# HB-UNI-SenAct-4-4-RC_V2_1.net
KiCad netlist of a schematic drawn in EAGLE
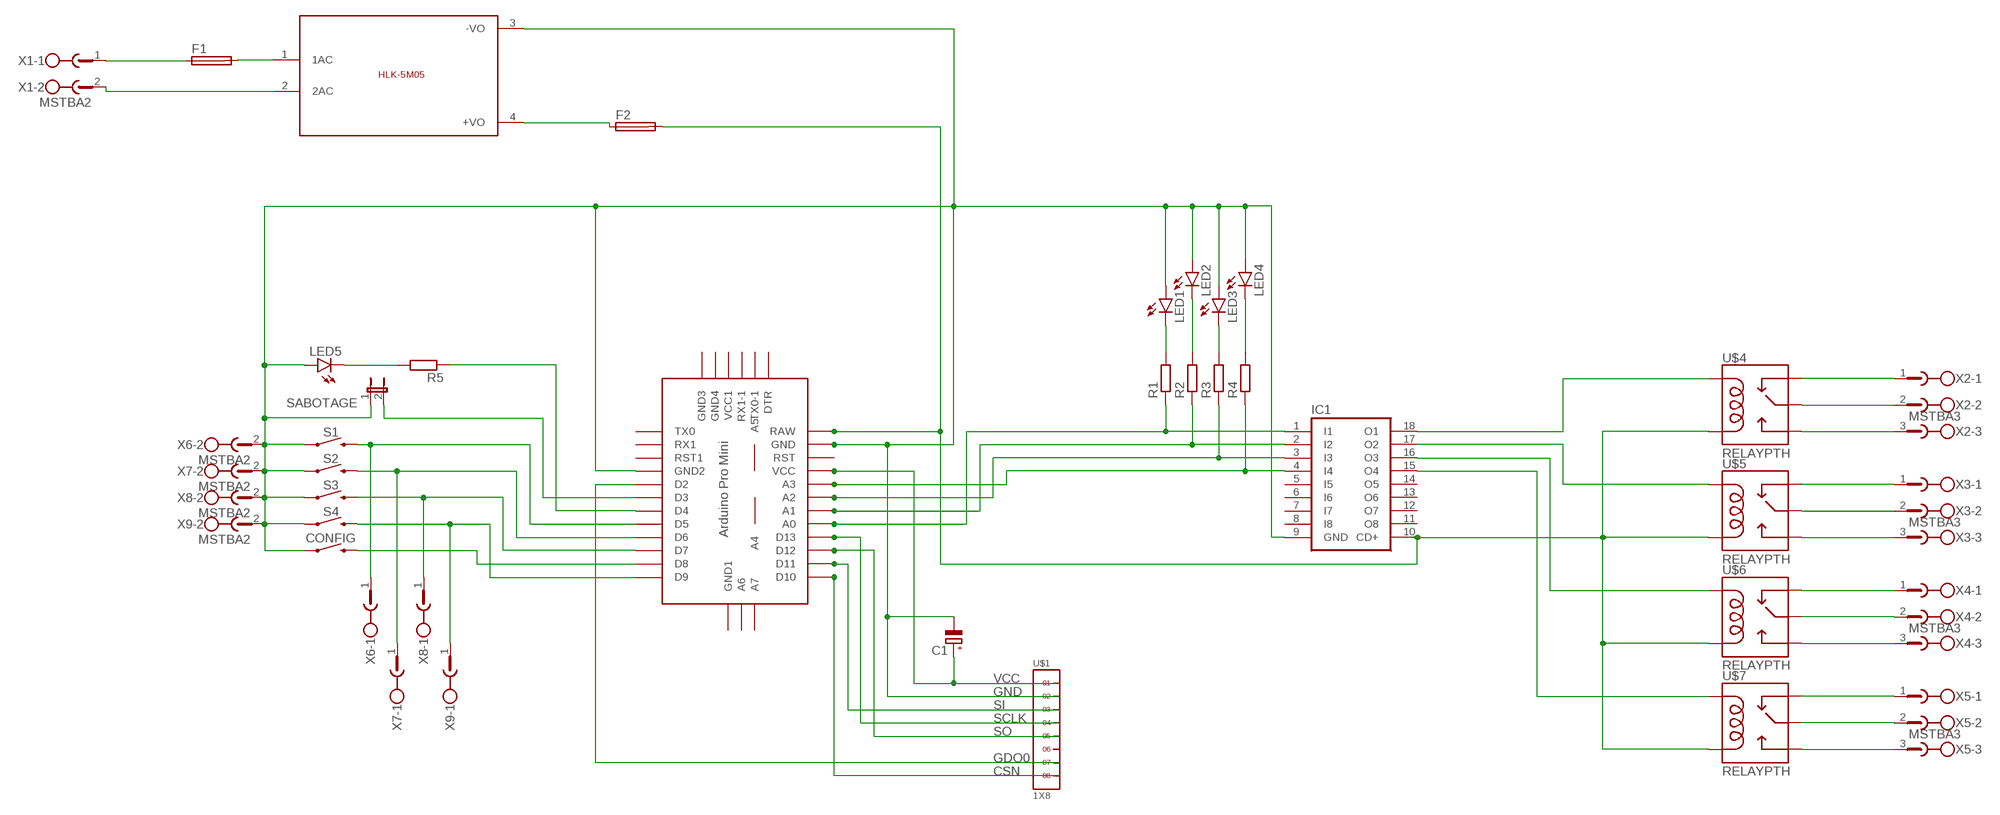
[diagram p0: schematic, sheet 1]

(export (version "E")
  (design (tool "Eeschema 10.0.6"))
  (components
    (comp (ref "C1")
      (value "CPOL-EUE2.5-5")
      (footprint "eagle-import:E2,5-5")
      (libsource (lib "eagle-import") (part "CPOL-EUE2.5-5"))
    )
    (comp (ref "CONFIG")
      (value "MOMENTARY-SWITCH-SPST-PTH-6.0MM-KIT")
      (footprint "eagle-import:TACTILE_SWITCH_PTH_6.0MM_KIT")
      (libsource (lib "eagle-import") (part "MOMENTARY-SWITCH-SPST-PTH-6.0MM-KIT"))
    )
    (comp (ref "F1")
      (value "SH22,5A")
      (footprint "eagle-import:SH22,5A")
      (fields (field (name "MPN") "0031.7701.11"))
      (libsource (lib "eagle-import") (part "SH22,5A"))
    )
    (comp (ref "F2")
      (value "SH22,5A")
      (footprint "eagle-import:SH22,5A")
      (fields (field (name "MPN") "0031.7701.11"))
      (libsource (lib "eagle-import") (part "SH22,5A"))
    )
    (comp (ref "IC1")
      (value "ULN2803A")
      (footprint "eagle-import:DIL18")
      (libsource (lib "eagle-import") (part "ULN2803A"))
    )
    (comp (ref "LED1")
      (value "LED3MM")
      (footprint "eagle-import:LED3MM")
      (libsource (lib "eagle-import") (part "LED3MM"))
    )
    (comp (ref "LED2")
      (value "LED3MM")
      (footprint "eagle-import:LED3MM")
      (libsource (lib "eagle-import") (part "LED3MM"))
    )
    (comp (ref "LED3")
      (value "LED3MM")
      (footprint "eagle-import:LED3MM")
      (libsource (lib "eagle-import") (part "LED3MM"))
    )
    (comp (ref "LED4")
      (value "LED3MM")
      (footprint "eagle-import:LED3MM")
      (libsource (lib "eagle-import") (part "LED3MM"))
    )
    (comp (ref "LED5")
      (value "LED3MM")
      (footprint "eagle-import:LED3MM")
      (libsource (lib "eagle-import") (part "LED3MM"))
    )
    (comp (ref "R1")
      (value "R-EU_0309/10")
      (footprint "eagle-import:0309_10")
      (libsource (lib "eagle-import") (part "R-EU_0309/10"))
    )
    (comp (ref "R2")
      (value "R-EU_0309/10")
      (footprint "eagle-import:0309_10")
      (libsource (lib "eagle-import") (part "R-EU_0309/10"))
    )
    (comp (ref "R3")
      (value "R-EU_0309/10")
      (footprint "eagle-import:0309_10")
      (libsource (lib "eagle-import") (part "R-EU_0309/10"))
    )
    (comp (ref "R4")
      (value "R-EU_0309/10")
      (footprint "eagle-import:0309_10")
      (libsource (lib "eagle-import") (part "R-EU_0309/10"))
    )
    (comp (ref "R5")
      (value "R-EU_0309/10")
      (footprint "eagle-import:0309_10")
      (libsource (lib "eagle-import") (part "R-EU_0309/10"))
    )
    (comp (ref "S1")
      (value "MOMENTARY-SWITCH-SPST-PTH-6.0MM")
      (footprint "eagle-import:TACTILE_SWITCH_PTH_6.0MM")
      (libsource (lib "eagle-import") (part "MOMENTARY-SWITCH-SPST-PTH-6.0MM"))
    )
    (comp (ref "S2")
      (value "MOMENTARY-SWITCH-SPST-PTH-6.0MM-KIT")
      (footprint "eagle-import:TACTILE_SWITCH_PTH_6.0MM_KIT")
      (libsource (lib "eagle-import") (part "MOMENTARY-SWITCH-SPST-PTH-6.0MM-KIT"))
    )
    (comp (ref "S3")
      (value "MOMENTARY-SWITCH-SPST-PTH-6.0MM-KIT")
      (footprint "eagle-import:TACTILE_SWITCH_PTH_6.0MM_KIT")
      (libsource (lib "eagle-import") (part "MOMENTARY-SWITCH-SPST-PTH-6.0MM-KIT"))
    )
    (comp (ref "S4")
      (value "MOMENTARY-SWITCH-SPST-PTH-6.0MM-KIT")
      (footprint "eagle-import:TACTILE_SWITCH_PTH_6.0MM_KIT")
      (libsource (lib "eagle-import") (part "MOMENTARY-SWITCH-SPST-PTH-6.0MM-KIT"))
    )
    (comp (ref "SABOTAGE")
      (value "JP1E")
      (footprint "eagle-import:JP1")
      (libsource (lib "eagle-import") (part "JP1E"))
    )
    (comp (ref "U$1")
      (value "1X8")
      (footprint "eagle-import:1X8")
      (libsource (lib "eagle-import") (part "1X8"))
    )
    (comp (ref "U$2")
      (value "ABK-PRO-MINI")
      (footprint "eagle-import:ABK-PRO-MINI")
      (libsource (lib "eagle-import") (part "ABK-PRO-MINI"))
    )
    (comp (ref "U$3")
      (value "5VDC/5W")
      (footprint "eagle-import:HLK-5M05")
      (libsource (lib "eagle-import") (part "HLK-5M05"))
    )
    (comp (ref "U$4")
      (value "RELAYPTH")
      (footprint "eagle-import:SRD-05VDC-SL-C")
      (libsource (lib "eagle-import") (part "RELAYPTH"))
    )
    (comp (ref "U$5")
      (value "RELAYPTH")
      (footprint "eagle-import:SRD-05VDC-SL-C")
      (libsource (lib "eagle-import") (part "RELAYPTH"))
    )
    (comp (ref "U$6")
      (value "RELAYPTH")
      (footprint "eagle-import:SRD-05VDC-SL-C")
      (libsource (lib "eagle-import") (part "RELAYPTH"))
    )
    (comp (ref "U$7")
      (value "RELAYPTH")
      (footprint "eagle-import:SRD-05VDC-SL-C")
      (libsource (lib "eagle-import") (part "RELAYPTH"))
    )
    (comp (ref "X1")
      (value "MSTBA2")
      (footprint "eagle-import:MSTBA2")
      (fields (field (name "MF") "FARNELL") (field (name "MPN") "1757242"))
      (libsource (lib "eagle-import") (part "MSTBA2"))
    )
    (comp (ref "X2")
      (value "MSTBA3")
      (footprint "eagle-import:MSTBA3")
      (fields (field (name "MF") "FARNELL") (field (name "MPN") "1757255"))
      (libsource (lib "eagle-import") (part "MSTBA3"))
    )
    (comp (ref "X3")
      (value "MSTBA3")
      (footprint "eagle-import:MSTBA3")
      (fields (field (name "MF") "FARNELL") (field (name "MPN") "1757255"))
      (libsource (lib "eagle-import") (part "MSTBA3"))
    )
    (comp (ref "X4")
      (value "MSTBA3")
      (footprint "eagle-import:MSTBA3")
      (fields (field (name "MF") "FARNELL") (field (name "MPN") "1757255"))
      (libsource (lib "eagle-import") (part "MSTBA3"))
    )
    (comp (ref "X5")
      (value "MSTBA3")
      (footprint "eagle-import:MSTBA3")
      (fields (field (name "MF") "FARNELL") (field (name "MPN") "1757255"))
      (libsource (lib "eagle-import") (part "MSTBA3"))
    )
    (comp (ref "X6")
      (value "MSTBA2")
      (footprint "eagle-import:MSTBA2")
      (fields (field (name "MF") "FARNELL") (field (name "MPN") "1757242"))
      (libsource (lib "eagle-import") (part "MSTBA2"))
    )
    (comp (ref "X7")
      (value "MSTBA2")
      (footprint "eagle-import:MSTBA2")
      (fields (field (name "MF") "FARNELL") (field (name "MPN") "1757242"))
      (libsource (lib "eagle-import") (part "MSTBA2"))
    )
    (comp (ref "X8")
      (value "MSTBA2")
      (footprint "eagle-import:MSTBA2")
      (fields (field (name "MF") "FARNELL") (field (name "MPN") "1757242"))
      (libsource (lib "eagle-import") (part "MSTBA2"))
    )
    (comp (ref "X9")
      (value "MSTBA2")
      (footprint "eagle-import:MSTBA2")
      (fields (field (name "MF") "FARNELL") (field (name "MPN") "1757242"))
      (libsource (lib "eagle-import") (part "MSTBA2"))
    )
  )
  (nets
    (net (code "1") (name "/CSN") (class "Default")
      (node (ref "U$1") (pin "8") (pinfunction "8_8") (pintype "bidirectional"))
      (node (ref "U$2") (pin "D10") (pinfunction "D10_D10") (pintype "bidirectional"))
    )
    (net (code "2") (name "/GDO0") (class "Default")
      (node (ref "U$1") (pin "7") (pinfunction "7_7") (pintype "bidirectional"))
      (node (ref "U$2") (pin "D2") (pinfunction "D2_D2") (pintype "bidirectional"))
    )
    (net (code "3") (name "/GND") (class "Default")
      (node (ref "C1") (pin "-") (pinfunction "-_-") (pintype "passive"))
      (node (ref "CONFIG") (pin "1") (pinfunction "1_1") (pintype "passive"))
      (node (ref "IC1") (pin "9") (pinfunction "GND_9") (pintype "power_in"))
      (node (ref "LED1") (pin "A") (pinfunction "A_A") (pintype "passive"))
      (node (ref "LED2") (pin "A") (pinfunction "A_A") (pintype "passive"))
      (node (ref "LED3") (pin "A") (pinfunction "A_A") (pintype "passive"))
      (node (ref "LED4") (pin "A") (pinfunction "A_A") (pintype "passive"))
      (node (ref "LED5") (pin "A") (pinfunction "A_A") (pintype "passive"))
      (node (ref "S1") (pin "1") (pinfunction "1_1") (pintype "passive"))
      (node (ref "S2") (pin "1") (pinfunction "1_1") (pintype "passive"))
      (node (ref "S3") (pin "1") (pinfunction "1_1") (pintype "passive"))
      (node (ref "S4") (pin "1") (pinfunction "1_1") (pintype "passive"))
      (node (ref "SABOTAGE") (pin "1") (pinfunction "1_1") (pintype "passive"))
      (node (ref "U$1") (pin "2") (pinfunction "2_2") (pintype "bidirectional"))
      (node (ref "U$2") (pin "GND") (pinfunction "GND_GND") (pintype "bidirectional"))
      (node (ref "U$2") (pin "GND1") (pinfunction "GND2_GND1") (pintype "bidirectional"))
      (node (ref "U$3") (pin "3") (pinfunction "-VO_3") (pintype "bidirectional"))
      (node (ref "X6") (pin "2") (pinfunction "1_2") (pintype "passive"))
      (node (ref "X7") (pin "2") (pinfunction "1_2") (pintype "passive"))
      (node (ref "X8") (pin "2") (pinfunction "1_2") (pintype "passive"))
      (node (ref "X9") (pin "2") (pinfunction "1_2") (pintype "passive"))
    )
    (net (code "4") (name "/SCLK") (class "Default")
      (node (ref "U$1") (pin "4") (pinfunction "4_4") (pintype "bidirectional"))
      (node (ref "U$2") (pin "D13") (pinfunction "D13_D13") (pintype "bidirectional"))
    )
    (net (code "5") (name "/SI") (class "Default")
      (node (ref "U$1") (pin "3") (pinfunction "3_3") (pintype "bidirectional"))
      (node (ref "U$2") (pin "D11") (pinfunction "D11_D11") (pintype "bidirectional"))
    )
    (net (code "6") (name "/SO") (class "Default")
      (node (ref "U$1") (pin "5") (pinfunction "5_5") (pintype "bidirectional"))
      (node (ref "U$2") (pin "D12") (pinfunction "D12_D12") (pintype "bidirectional"))
    )
    (net (code "7") (name "/VCC") (class "Default")
      (node (ref "C1") (pin "+") (pinfunction "+_+") (pintype "passive"))
      (node (ref "U$1") (pin "1") (pinfunction "1_1") (pintype "bidirectional"))
      (node (ref "U$2") (pin "VCC") (pinfunction "VCC_VCC") (pintype "bidirectional"))
    )
    (net (code "8") (name "Net-(CONFIG-2)") (class "Default")
      (node (ref "CONFIG") (pin "3") (pinfunction "2_3") (pintype "passive"))
      (node (ref "U$2") (pin "D8") (pinfunction "D8_D8") (pintype "bidirectional"))
    )
    (net (code "9") (name "Net-(F1-Pad1)") (class "Default")
      (node (ref "F1") (pin "1") (pinfunction "1_1") (pintype "passive"))
      (node (ref "X1") (pin "1") (pinfunction "1_1") (pintype "passive"))
    )
    (net (code "10") (name "Net-(IC1-CD+)") (class "Default")
      (node (ref "F2") (pin "2") (pinfunction "2_2") (pintype "passive"))
      (node (ref "IC1") (pin "10") (pinfunction "CD+_10") (pintype "passive"))
      (node (ref "U$2") (pin "RAW") (pinfunction "RAW_RAW") (pintype "bidirectional"))
      (node (ref "U$4") (pin "COIL0") (pinfunction "COIL0_COIL0") (pintype "bidirectional"))
      (node (ref "U$5") (pin "COIL0") (pinfunction "COIL0_COIL0") (pintype "bidirectional"))
      (node (ref "U$6") (pin "COIL0") (pinfunction "COIL0_COIL0") (pintype "bidirectional"))
      (node (ref "U$7") (pin "COIL0") (pinfunction "COIL0_COIL0") (pintype "bidirectional"))
    )
    (net (code "11") (name "Net-(IC1-I1)") (class "Default")
      (node (ref "IC1") (pin "1") (pinfunction "I1_1") (pintype "input"))
      (node (ref "R1") (pin "1") (pinfunction "1_1") (pintype "passive"))
      (node (ref "U$2") (pin "A0") (pinfunction "A0_A0") (pintype "bidirectional"))
    )
    (net (code "12") (name "Net-(IC1-I2)") (class "Default")
      (node (ref "IC1") (pin "2") (pinfunction "I2_2") (pintype "input"))
      (node (ref "R2") (pin "1") (pinfunction "1_1") (pintype "passive"))
      (node (ref "U$2") (pin "A1") (pinfunction "A1_A1") (pintype "bidirectional"))
    )
    (net (code "13") (name "Net-(IC1-I3)") (class "Default")
      (node (ref "IC1") (pin "3") (pinfunction "I3_3") (pintype "input"))
      (node (ref "R3") (pin "1") (pinfunction "1_1") (pintype "passive"))
      (node (ref "U$2") (pin "A2") (pinfunction "A2_A2") (pintype "bidirectional"))
    )
    (net (code "14") (name "Net-(IC1-I4)") (class "Default")
      (node (ref "IC1") (pin "4") (pinfunction "I4_4") (pintype "input"))
      (node (ref "R4") (pin "1") (pinfunction "1_1") (pintype "passive"))
      (node (ref "U$2") (pin "A3") (pinfunction "A3_A3") (pintype "bidirectional"))
    )
    (net (code "15") (name "Net-(IC1-O1)") (class "Default")
      (node (ref "IC1") (pin "18") (pinfunction "O1_18") (pintype "open_collector"))
      (node (ref "U$4") (pin "COIL1") (pinfunction "COIL1_COIL1") (pintype "bidirectional"))
    )
    (net (code "16") (name "Net-(IC1-O2)") (class "Default")
      (node (ref "IC1") (pin "17") (pinfunction "O2_17") (pintype "open_collector"))
      (node (ref "U$5") (pin "COIL1") (pinfunction "COIL1_COIL1") (pintype "bidirectional"))
    )
    (net (code "17") (name "Net-(IC1-O3)") (class "Default")
      (node (ref "IC1") (pin "16") (pinfunction "O3_16") (pintype "open_collector"))
      (node (ref "U$6") (pin "COIL1") (pinfunction "COIL1_COIL1") (pintype "bidirectional"))
    )
    (net (code "18") (name "Net-(IC1-O4)") (class "Default")
      (node (ref "IC1") (pin "15") (pinfunction "O4_15") (pintype "open_collector"))
      (node (ref "U$7") (pin "COIL1") (pinfunction "COIL1_COIL1") (pintype "bidirectional"))
    )
    (net (code "19") (name "Net-(LED1-C)") (class "Default")
      (node (ref "LED1") (pin "K") (pinfunction "C_K") (pintype "passive"))
      (node (ref "R1") (pin "2") (pinfunction "2_2") (pintype "passive"))
    )
    (net (code "20") (name "Net-(LED2-C)") (class "Default")
      (node (ref "LED2") (pin "K") (pinfunction "C_K") (pintype "passive"))
      (node (ref "R2") (pin "2") (pinfunction "2_2") (pintype "passive"))
    )
    (net (code "21") (name "Net-(LED3-C)") (class "Default")
      (node (ref "LED3") (pin "K") (pinfunction "C_K") (pintype "passive"))
      (node (ref "R3") (pin "2") (pinfunction "2_2") (pintype "passive"))
    )
    (net (code "22") (name "Net-(LED4-C)") (class "Default")
      (node (ref "LED4") (pin "K") (pinfunction "C_K") (pintype "passive"))
      (node (ref "R4") (pin "2") (pinfunction "2_2") (pintype "passive"))
    )
    (net (code "23") (name "Net-(LED5-C)") (class "Default")
      (node (ref "LED5") (pin "K") (pinfunction "C_K") (pintype "passive"))
      (node (ref "R5") (pin "2") (pinfunction "2_2") (pintype "passive"))
    )
    (net (code "24") (name "Net-(R5-Pad1)") (class "Default")
      (node (ref "R5") (pin "1") (pinfunction "1_1") (pintype "passive"))
      (node (ref "U$2") (pin "D4") (pinfunction "D4_D4") (pintype "bidirectional"))
    )
    (net (code "25") (name "Net-(S1-2)") (class "Default")
      (node (ref "S1") (pin "3") (pinfunction "2_3") (pintype "passive"))
      (node (ref "U$2") (pin "D5") (pinfunction "D5_D5") (pintype "bidirectional"))
      (node (ref "X6") (pin "1") (pinfunction "1_1") (pintype "passive"))
    )
    (net (code "26") (name "Net-(S2-2)") (class "Default")
      (node (ref "S2") (pin "3") (pinfunction "2_3") (pintype "passive"))
      (node (ref "U$2") (pin "D6") (pinfunction "D6_D6") (pintype "bidirectional"))
      (node (ref "X7") (pin "1") (pinfunction "1_1") (pintype "passive"))
    )
    (net (code "27") (name "Net-(S3-2)") (class "Default")
      (node (ref "S3") (pin "3") (pinfunction "2_3") (pintype "passive"))
      (node (ref "U$2") (pin "D7") (pinfunction "D7_D7") (pintype "bidirectional"))
      (node (ref "X8") (pin "1") (pinfunction "1_1") (pintype "passive"))
    )
    (net (code "28") (name "Net-(S4-2)") (class "Default")
      (node (ref "S4") (pin "3") (pinfunction "2_3") (pintype "passive"))
      (node (ref "U$2") (pin "D9") (pinfunction "D9_D9") (pintype "bidirectional"))
      (node (ref "X9") (pin "1") (pinfunction "1_1") (pintype "passive"))
    )
    (net (code "29") (name "Net-(SABOTAGE-Pad2)") (class "Default")
      (node (ref "SABOTAGE") (pin "2") (pinfunction "2_2") (pintype "passive"))
      (node (ref "U$2") (pin "D3") (pinfunction "D3_D3") (pintype "bidirectional"))
    )
    (net (code "30") (name "Net-(U$3-+VO)") (class "Default")
      (node (ref "F2") (pin "1") (pinfunction "1_1") (pintype "passive"))
      (node (ref "U$3") (pin "4") (pinfunction "+VO_4") (pintype "bidirectional"))
    )
    (net (code "31") (name "Net-(U$3-1AC)") (class "Default")
      (node (ref "F1") (pin "2") (pinfunction "2_2") (pintype "passive"))
      (node (ref "U$3") (pin "1") (pinfunction "1AC_1") (pintype "bidirectional"))
    )
    (net (code "32") (name "Net-(U$3-2AC)") (class "Default")
      (node (ref "U$3") (pin "2") (pinfunction "2AC_2") (pintype "bidirectional"))
      (node (ref "X1") (pin "2") (pinfunction "1_2") (pintype "passive"))
    )
    (net (code "33") (name "Net-(U$4-SWCLOSE)") (class "Default")
      (node (ref "U$4") (pin "SWCLOSED") (pinfunction "SWCLOSE_SWCLOSED") (pintype "bidirectional"))
      (node (ref "X2") (pin "1") (pinfunction "1_1") (pintype "passive"))
    )
    (net (code "34") (name "Net-(U$5-SWCLOSE)") (class "Default")
      (node (ref "U$5") (pin "SWCLOSED") (pinfunction "SWCLOSE_SWCLOSED") (pintype "bidirectional"))
      (node (ref "X3") (pin "1") (pinfunction "1_1") (pintype "passive"))
    )
    (net (code "35") (name "Net-(U$6-SWCLOSE)") (class "Default")
      (node (ref "U$6") (pin "SWCLOSED") (pinfunction "SWCLOSE_SWCLOSED") (pintype "bidirectional"))
      (node (ref "X4") (pin "1") (pinfunction "1_1") (pintype "passive"))
    )
    (net (code "36") (name "Net-(U$7-SWCLOSE)") (class "Default")
      (node (ref "U$7") (pin "SWCLOSED") (pinfunction "SWCLOSE_SWCLOSED") (pintype "bidirectional"))
      (node (ref "X5") (pin "1") (pinfunction "1_1") (pintype "passive"))
    )
    (net (code "37") (name "Net-(X2B-1)") (class "Default")
      (node (ref "U$4") (pin "SWCOMMON") (pinfunction "SWCOMMON_SWCOMMON") (pintype "bidirectional"))
      (node (ref "X2") (pin "2") (pinfunction "1_2") (pintype "passive"))
    )
    (net (code "38") (name "Net-(X2C-1)") (class "Default")
      (node (ref "U$4") (pin "SWOPEN") (pinfunction "SWOPEN_SWOPEN") (pintype "bidirectional"))
      (node (ref "X2") (pin "3") (pinfunction "1_3") (pintype "passive"))
    )
    (net (code "39") (name "Net-(X3B-1)") (class "Default")
      (node (ref "U$5") (pin "SWCOMMON") (pinfunction "SWCOMMON_SWCOMMON") (pintype "bidirectional"))
      (node (ref "X3") (pin "2") (pinfunction "1_2") (pintype "passive"))
    )
    (net (code "40") (name "Net-(X3C-1)") (class "Default")
      (node (ref "U$5") (pin "SWOPEN") (pinfunction "SWOPEN_SWOPEN") (pintype "bidirectional"))
      (node (ref "X3") (pin "3") (pinfunction "1_3") (pintype "passive"))
    )
    (net (code "41") (name "Net-(X4B-1)") (class "Default")
      (node (ref "U$6") (pin "SWCOMMON") (pinfunction "SWCOMMON_SWCOMMON") (pintype "bidirectional"))
      (node (ref "X4") (pin "2") (pinfunction "1_2") (pintype "passive"))
    )
    (net (code "42") (name "Net-(X4C-1)") (class "Default")
      (node (ref "U$6") (pin "SWOPEN") (pinfunction "SWOPEN_SWOPEN") (pintype "bidirectional"))
      (node (ref "X4") (pin "3") (pinfunction "1_3") (pintype "passive"))
    )
    (net (code "43") (name "Net-(X5B-1)") (class "Default")
      (node (ref "U$7") (pin "SWCOMMON") (pinfunction "SWCOMMON_SWCOMMON") (pintype "bidirectional"))
      (node (ref "X5") (pin "2") (pinfunction "1_2") (pintype "passive"))
    )
    (net (code "44") (name "Net-(X5C-1)") (class "Default")
      (node (ref "U$7") (pin "SWOPEN") (pinfunction "SWOPEN_SWOPEN") (pintype "bidirectional"))
      (node (ref "X5") (pin "3") (pinfunction "1_3") (pintype "passive"))
    )
    (net (code "45") (name "unconnected-(IC1-I5-Pad5)") (class "Default")
      (node (ref "IC1") (pin "5") (pinfunction "I5_5") (pintype "input"))
    )
    (net (code "46") (name "unconnected-(IC1-I6-Pad6)") (class "Default")
      (node (ref "IC1") (pin "6") (pinfunction "I6_6") (pintype "input"))
    )
    (net (code "47") (name "unconnected-(IC1-I7-Pad7)") (class "Default")
      (node (ref "IC1") (pin "7") (pinfunction "I7_7") (pintype "input"))
    )
    (net (code "48") (name "unconnected-(IC1-I8-Pad8)") (class "Default")
      (node (ref "IC1") (pin "8") (pinfunction "I8_8") (pintype "input"))
    )
    (net (code "49") (name "unconnected-(IC1-O5-Pad14)") (class "Default")
      (node (ref "IC1") (pin "14") (pinfunction "O5_14") (pintype "open_collector"))
    )
    (net (code "50") (name "unconnected-(IC1-O6-Pad13)") (class "Default")
      (node (ref "IC1") (pin "13") (pinfunction "O6_13") (pintype "open_collector"))
    )
    (net (code "51") (name "unconnected-(IC1-O7-Pad12)") (class "Default")
      (node (ref "IC1") (pin "12") (pinfunction "O7_12") (pintype "open_collector"))
    )
    (net (code "52") (name "unconnected-(IC1-O8-Pad11)") (class "Default")
      (node (ref "IC1") (pin "11") (pinfunction "O8_11") (pintype "open_collector"))
    )
    (net (code "53") (name "unconnected-(U$1-Pad6)") (class "Default")
      (node (ref "U$1") (pin "6") (pinfunction "6_6") (pintype "bidirectional"))
    )
    (net (code "54") (name "unconnected-(U$2-GND1-PadGND4)") (class "Default")
      (node (ref "U$2") (pin "GND4") (pinfunction "GND1_GND4") (pintype "bidirectional"))
    )
    (net (code "55") (name "unconnected-(U$2-GND3-PadGND2)") (class "Default")
      (node (ref "U$2") (pin "GND2") (pinfunction "GND3_GND2") (pintype "bidirectional"))
    )
    (net (code "56") (name "unconnected-(U$2-GND4-PadGND3)") (class "Default")
      (node (ref "U$2") (pin "GND3") (pinfunction "GND4_GND3") (pintype "bidirectional"))
    )
    (net (code "57") (name "unconnected-(U$2-PadA4)") (class "Default")
      (node (ref "U$2") (pin "A4") (pinfunction "A4_A4") (pintype "bidirectional"))
    )
    (net (code "58") (name "unconnected-(U$2-PadA5)") (class "Default")
      (node (ref "U$2") (pin "A5") (pinfunction "A5_A5") (pintype "bidirectional"))
    )
    (net (code "59") (name "unconnected-(U$2-PadA6)") (class "Default")
      (node (ref "U$2") (pin "A6") (pinfunction "A6_A6") (pintype "bidirectional"))
    )
    (net (code "60") (name "unconnected-(U$2-PadA7)") (class "Default")
      (node (ref "U$2") (pin "A7") (pinfunction "A7_A7") (pintype "bidirectional"))
    )
    (net (code "61") (name "unconnected-(U$2-PadDTR)") (class "Default")
      (node (ref "U$2") (pin "DTR") (pinfunction "DTR_DTR") (pintype "bidirectional"))
    )
    (net (code "62") (name "unconnected-(U$2-PadRST)") (class "Default")
      (node (ref "U$2") (pin "RST") (pinfunction "RST_RST") (pintype "bidirectional"))
    )
    (net (code "63") (name "unconnected-(U$2-PadRST1)") (class "Default")
      (node (ref "U$2") (pin "RST1") (pinfunction "RST1_RST1") (pintype "bidirectional"))
    )
    (net (code "64") (name "unconnected-(U$2-PadRX1)") (class "Default")
      (node (ref "U$2") (pin "RX1") (pinfunction "RX1_RX1") (pintype "bidirectional"))
    )
    (net (code "65") (name "unconnected-(U$2-PadRX1-1)") (class "Default")
      (node (ref "U$2") (pin "RX1-1") (pinfunction "RX1-1_RX1-1") (pintype "bidirectional"))
    )
    (net (code "66") (name "unconnected-(U$2-PadTX0)") (class "Default")
      (node (ref "U$2") (pin "TX0") (pinfunction "TX0_TX0") (pintype "bidirectional"))
    )
    (net (code "67") (name "unconnected-(U$2-PadTX0-1)") (class "Default")
      (node (ref "U$2") (pin "TX0-1") (pinfunction "TX0-1_TX0-1") (pintype "bidirectional"))
    )
    (net (code "68") (name "unconnected-(U$2-PadVCC1)") (class "Default")
      (node (ref "U$2") (pin "VCC1") (pinfunction "VCC1_VCC1") (pintype "bidirectional"))
    )
  )
)
